# ASD2004.net
KiCad netlist of a schematic drawn in EAGLE
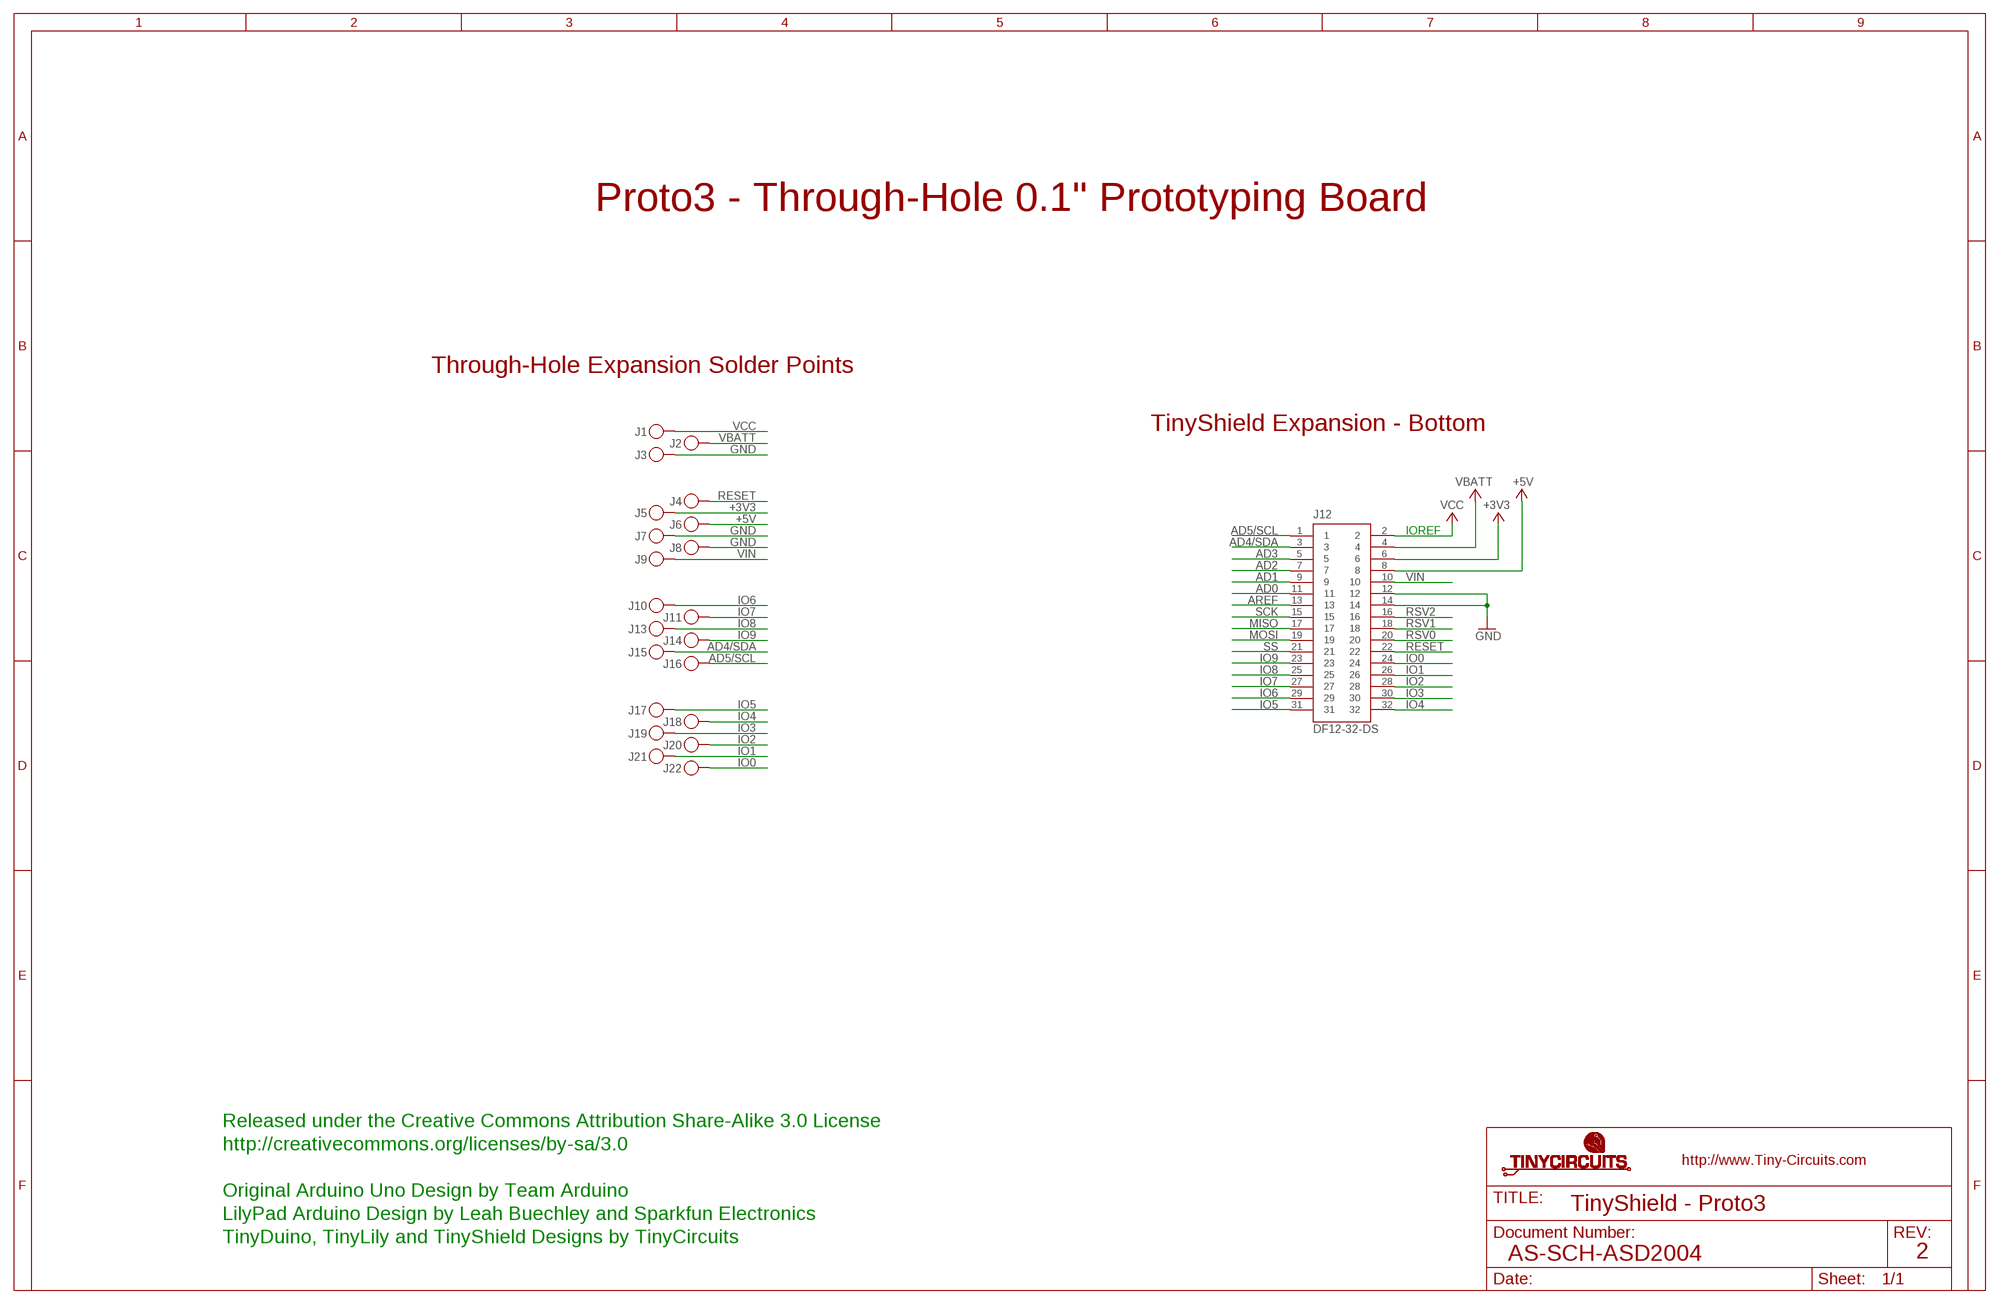
[diagram p0: schematic, sheet 1]

(export (version "E")
  (design (tool "Eeschema 10.0.6"))
  (components
    (comp (ref "J1")
      (value "PIN_1X.1\"1")
      (footprint "eagle-import:1X.1__2")
      (fields (field (name "PARTNO") "COPPER"))
      (libsource (lib "eagle-import") (part "PIN_1X.1{dblquote}1"))
    )
    (comp (ref "J2")
      (value "PIN_1X.1\"1")
      (footprint "eagle-import:1X.1__2")
      (fields (field (name "PARTNO") "COPPER"))
      (libsource (lib "eagle-import") (part "PIN_1X.1{dblquote}1"))
    )
    (comp (ref "J3")
      (value "PIN_1X.1\"1")
      (footprint "eagle-import:1X.1__2")
      (fields (field (name "PARTNO") "COPPER"))
      (libsource (lib "eagle-import") (part "PIN_1X.1{dblquote}1"))
    )
    (comp (ref "J4")
      (value "PIN_1X.1\"1")
      (footprint "eagle-import:1X.1__2")
      (fields (field (name "PARTNO") "COPPER"))
      (libsource (lib "eagle-import") (part "PIN_1X.1{dblquote}1"))
    )
    (comp (ref "J5")
      (value "PIN_1X.1\"1")
      (footprint "eagle-import:1X.1__2")
      (fields (field (name "PARTNO") "COPPER"))
      (libsource (lib "eagle-import") (part "PIN_1X.1{dblquote}1"))
    )
    (comp (ref "J6")
      (value "PIN_1X.1\"1")
      (footprint "eagle-import:1X.1__2")
      (fields (field (name "PARTNO") "COPPER"))
      (libsource (lib "eagle-import") (part "PIN_1X.1{dblquote}1"))
    )
    (comp (ref "J7")
      (value "PIN_1X.1\"1")
      (footprint "eagle-import:1X.1__2")
      (fields (field (name "PARTNO") "COPPER"))
      (libsource (lib "eagle-import") (part "PIN_1X.1{dblquote}1"))
    )
    (comp (ref "J8")
      (value "PIN_1X.1\"1")
      (footprint "eagle-import:1X.1__2")
      (fields (field (name "PARTNO") "COPPER"))
      (libsource (lib "eagle-import") (part "PIN_1X.1{dblquote}1"))
    )
    (comp (ref "J9")
      (value "PIN_1X.1\"1")
      (footprint "eagle-import:1X.1__2")
      (fields (field (name "PARTNO") "COPPER"))
      (libsource (lib "eagle-import") (part "PIN_1X.1{dblquote}1"))
    )
    (comp (ref "J10")
      (value "PIN_1X.1\"1")
      (footprint "eagle-import:1X.1__2")
      (fields (field (name "PARTNO") "COPPER"))
      (libsource (lib "eagle-import") (part "PIN_1X.1{dblquote}1"))
    )
    (comp (ref "J11")
      (value "PIN_1X.1\"1")
      (footprint "eagle-import:1X.1__2")
      (fields (field (name "PARTNO") "COPPER"))
      (libsource (lib "eagle-import") (part "PIN_1X.1{dblquote}1"))
    )
    (comp (ref "J12")
      (value "DF12-32-DS")
      (footprint "eagle-import:DF12-32-DS")
      (fields (field (name "PARTNO") "AS-ITM-00012") (field (name "PARTNO_1") "AS-ITM-00012"))
      (libsource (lib "eagle-import") (part "AS-ITM-00012"))
    )
    (comp (ref "J13")
      (value "PIN_1X.1\"1")
      (footprint "eagle-import:1X.1__2")
      (fields (field (name "PARTNO") "COPPER"))
      (libsource (lib "eagle-import") (part "PIN_1X.1{dblquote}1"))
    )
    (comp (ref "J14")
      (value "PIN_1X.1\"1")
      (footprint "eagle-import:1X.1__2")
      (fields (field (name "PARTNO") "COPPER"))
      (libsource (lib "eagle-import") (part "PIN_1X.1{dblquote}1"))
    )
    (comp (ref "J15")
      (value "PIN_1X.1\"1")
      (footprint "eagle-import:1X.1__2")
      (fields (field (name "PARTNO") "COPPER"))
      (libsource (lib "eagle-import") (part "PIN_1X.1{dblquote}1"))
    )
    (comp (ref "J16")
      (value "PIN_1X.1\"1")
      (footprint "eagle-import:1X.1__2")
      (fields (field (name "PARTNO") "COPPER"))
      (libsource (lib "eagle-import") (part "PIN_1X.1{dblquote}1"))
    )
    (comp (ref "J17")
      (value "PIN_1X.1\"1")
      (footprint "eagle-import:1X.1__2")
      (fields (field (name "PARTNO") "COPPER"))
      (libsource (lib "eagle-import") (part "PIN_1X.1{dblquote}1"))
    )
    (comp (ref "J18")
      (value "PIN_1X.1\"1")
      (footprint "eagle-import:1X.1__2")
      (fields (field (name "PARTNO") "COPPER"))
      (libsource (lib "eagle-import") (part "PIN_1X.1{dblquote}1"))
    )
    (comp (ref "J19")
      (value "PIN_1X.1\"1")
      (footprint "eagle-import:1X.1__2")
      (fields (field (name "PARTNO") "COPPER"))
      (libsource (lib "eagle-import") (part "PIN_1X.1{dblquote}1"))
    )
    (comp (ref "J20")
      (value "PIN_1X.1\"1")
      (footprint "eagle-import:1X.1__2")
      (fields (field (name "PARTNO") "COPPER"))
      (libsource (lib "eagle-import") (part "PIN_1X.1{dblquote}1"))
    )
    (comp (ref "J21")
      (value "PIN_1X.1\"1")
      (footprint "eagle-import:1X.1__2")
      (fields (field (name "PARTNO") "COPPER"))
      (libsource (lib "eagle-import") (part "PIN_1X.1{dblquote}1"))
    )
    (comp (ref "J22")
      (value "PIN_1X.1\"1")
      (footprint "eagle-import:1X.1__2")
      (fields (field (name "PARTNO") "COPPER"))
      (libsource (lib "eagle-import") (part "PIN_1X.1{dblquote}1"))
    )
  )
  (nets
    (net (code "1") (name "+3V3") (class "Default")
      (node (ref "J12") (pin "6") (pinfunction "6_6") (pintype "bidirectional"))
      (node (ref "J5") (pin "1") (pinfunction "1_1") (pintype "bidirectional"))
    )
    (net (code "2") (name "+5V") (class "Default")
      (node (ref "J12") (pin "8") (pinfunction "8_8") (pintype "bidirectional"))
      (node (ref "J6") (pin "1") (pinfunction "1_1") (pintype "bidirectional"))
    )
    (net (code "3") (name "/AD0") (class "Default")
      (node (ref "J12") (pin "11") (pinfunction "11_11") (pintype "bidirectional"))
    )
    (net (code "4") (name "/AD1") (class "Default")
      (node (ref "J12") (pin "9") (pinfunction "9_9") (pintype "bidirectional"))
    )
    (net (code "5") (name "/AD2") (class "Default")
      (node (ref "J12") (pin "7") (pinfunction "7_7") (pintype "bidirectional"))
    )
    (net (code "6") (name "/AD3") (class "Default")
      (node (ref "J12") (pin "5") (pinfunction "5_5") (pintype "bidirectional"))
    )
    (net (code "7") (name "/AD4{slash}SDA") (class "Default")
      (node (ref "J12") (pin "3") (pinfunction "3_3") (pintype "bidirectional"))
      (node (ref "J15") (pin "1") (pinfunction "1_1") (pintype "bidirectional"))
    )
    (net (code "8") (name "/AD5{slash}SCL") (class "Default")
      (node (ref "J12") (pin "1") (pinfunction "1_1") (pintype "bidirectional"))
      (node (ref "J16") (pin "1") (pinfunction "1_1") (pintype "bidirectional"))
    )
    (net (code "9") (name "/AREF") (class "Default")
      (node (ref "J12") (pin "13") (pinfunction "13_13") (pintype "bidirectional"))
    )
    (net (code "10") (name "/IO0") (class "Default")
      (node (ref "J12") (pin "24") (pinfunction "24_24") (pintype "bidirectional"))
      (node (ref "J22") (pin "1") (pinfunction "1_1") (pintype "bidirectional"))
    )
    (net (code "11") (name "/IO1") (class "Default")
      (node (ref "J12") (pin "26") (pinfunction "26_26") (pintype "bidirectional"))
      (node (ref "J21") (pin "1") (pinfunction "1_1") (pintype "bidirectional"))
    )
    (net (code "12") (name "/IO2") (class "Default")
      (node (ref "J12") (pin "28") (pinfunction "28_28") (pintype "bidirectional"))
      (node (ref "J20") (pin "1") (pinfunction "1_1") (pintype "bidirectional"))
    )
    (net (code "13") (name "/IO3") (class "Default")
      (node (ref "J12") (pin "30") (pinfunction "30_30") (pintype "bidirectional"))
      (node (ref "J19") (pin "1") (pinfunction "1_1") (pintype "bidirectional"))
    )
    (net (code "14") (name "/IO4") (class "Default")
      (node (ref "J12") (pin "32") (pinfunction "32_32") (pintype "bidirectional"))
      (node (ref "J18") (pin "1") (pinfunction "1_1") (pintype "bidirectional"))
    )
    (net (code "15") (name "/IO5") (class "Default")
      (node (ref "J12") (pin "31") (pinfunction "31_31") (pintype "bidirectional"))
      (node (ref "J17") (pin "1") (pinfunction "1_1") (pintype "bidirectional"))
    )
    (net (code "16") (name "/IO6") (class "Default")
      (node (ref "J10") (pin "1") (pinfunction "1_1") (pintype "bidirectional"))
      (node (ref "J12") (pin "29") (pinfunction "29_29") (pintype "bidirectional"))
    )
    (net (code "17") (name "/IO7") (class "Default")
      (node (ref "J11") (pin "1") (pinfunction "1_1") (pintype "bidirectional"))
      (node (ref "J12") (pin "27") (pinfunction "27_27") (pintype "bidirectional"))
    )
    (net (code "18") (name "/IO8") (class "Default")
      (node (ref "J12") (pin "25") (pinfunction "25_25") (pintype "bidirectional"))
      (node (ref "J13") (pin "1") (pinfunction "1_1") (pintype "bidirectional"))
    )
    (net (code "19") (name "/IO9") (class "Default")
      (node (ref "J12") (pin "23") (pinfunction "23_23") (pintype "bidirectional"))
      (node (ref "J14") (pin "1") (pinfunction "1_1") (pintype "bidirectional"))
    )
    (net (code "20") (name "/MISO") (class "Default")
      (node (ref "J12") (pin "17") (pinfunction "17_17") (pintype "bidirectional"))
    )
    (net (code "21") (name "/MOSI") (class "Default")
      (node (ref "J12") (pin "19") (pinfunction "19_19") (pintype "bidirectional"))
    )
    (net (code "22") (name "/RESET") (class "Default")
      (node (ref "J12") (pin "22") (pinfunction "22_22") (pintype "bidirectional"))
      (node (ref "J4") (pin "1") (pinfunction "1_1") (pintype "bidirectional"))
    )
    (net (code "23") (name "/RSV0") (class "Default")
      (node (ref "J12") (pin "20") (pinfunction "20_20") (pintype "bidirectional"))
    )
    (net (code "24") (name "/RSV1") (class "Default")
      (node (ref "J12") (pin "18") (pinfunction "18_18") (pintype "bidirectional"))
    )
    (net (code "25") (name "/RSV2") (class "Default")
      (node (ref "J12") (pin "16") (pinfunction "16_16") (pintype "bidirectional"))
    )
    (net (code "26") (name "/SCK") (class "Default")
      (node (ref "J12") (pin "15") (pinfunction "15_15") (pintype "bidirectional"))
    )
    (net (code "27") (name "/SS") (class "Default")
      (node (ref "J12") (pin "21") (pinfunction "21_21") (pintype "bidirectional"))
    )
    (net (code "28") (name "/VIN") (class "Default")
      (node (ref "J12") (pin "10") (pinfunction "10_10") (pintype "bidirectional"))
      (node (ref "J9") (pin "1") (pinfunction "1_1") (pintype "bidirectional"))
    )
    (net (code "29") (name "GND") (class "Default")
      (node (ref "J12") (pin "12") (pinfunction "12_12") (pintype "bidirectional"))
      (node (ref "J12") (pin "14") (pinfunction "14_14") (pintype "bidirectional"))
      (node (ref "J3") (pin "1") (pinfunction "1_1") (pintype "bidirectional"))
      (node (ref "J7") (pin "1") (pinfunction "1_1") (pintype "bidirectional"))
      (node (ref "J8") (pin "1") (pinfunction "1_1") (pintype "bidirectional"))
    )
    (net (code "30") (name "VBATT") (class "Default")
      (node (ref "J12") (pin "4") (pinfunction "4_4") (pintype "bidirectional"))
      (node (ref "J2") (pin "1") (pinfunction "1_1") (pintype "bidirectional"))
    )
    (net (code "31") (name "VCC") (class "Default")
      (node (ref "J1") (pin "1") (pinfunction "1_1") (pintype "bidirectional"))
      (node (ref "J12") (pin "2") (pinfunction "2_2") (pintype "bidirectional"))
    )
  )
)
